# IMU.net
KiCad netlist of a schematic drawn in EAGLE
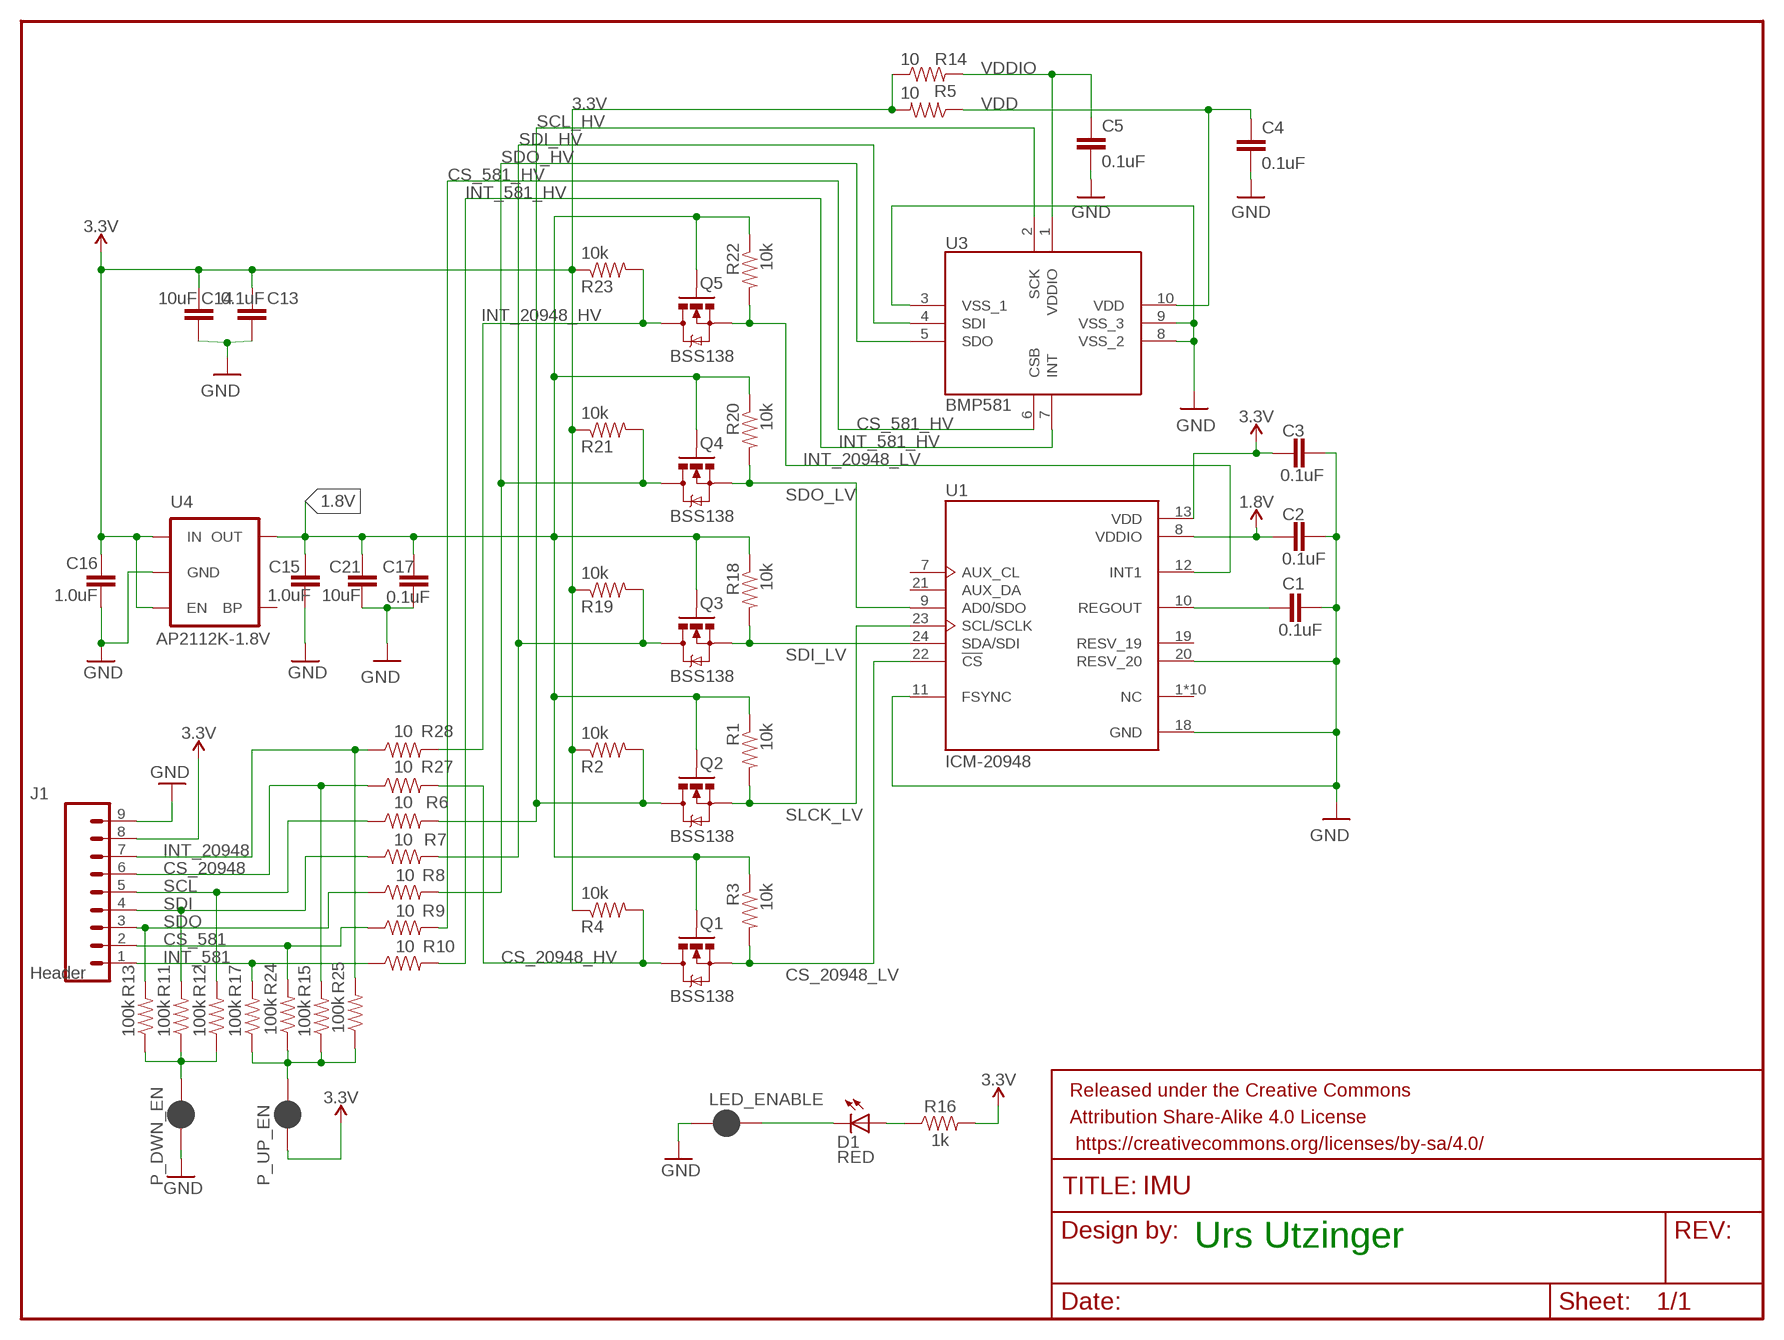
[diagram p0: schematic, sheet 1]

(export (version "E")
  (design (tool "Eeschema 10.0.6"))
  (components
    (comp (ref "C1")
      (value "0.1uF")
      (footprint "eagle-import:0603")
      (libsource (lib "eagle-import") (part "0.1UF-0603-25V-(+80/-20%)"))
    )
    (comp (ref "C2")
      (value "0.1uF")
      (footprint "eagle-import:0603")
      (libsource (lib "eagle-import") (part "0.1UF-0603-25V-(+80/-20%)"))
    )
    (comp (ref "C3")
      (value "0.1uF")
      (footprint "eagle-import:0603")
      (libsource (lib "eagle-import") (part "0.1UF-0603-25V-(+80/-20%)"))
    )
    (comp (ref "C4")
      (value "0.1uF")
      (footprint "eagle-import:0603")
      (libsource (lib "eagle-import") (part "0.1UF-0603-25V-(+80/-20%)"))
    )
    (comp (ref "C5")
      (value "0.1uF")
      (footprint "eagle-import:0603")
      (libsource (lib "eagle-import") (part "0.1UF-0603-25V-(+80/-20%)"))
    )
    (comp (ref "C13")
      (value "0.1uF")
      (footprint "eagle-import:0603")
      (libsource (lib "eagle-import") (part "0.1UF-0603-25V-(+80/-20%)"))
    )
    (comp (ref "C14")
      (value "10uF")
      (footprint "eagle-import:0603@1")
      (libsource (lib "eagle-import") (part "10UF-0603-6.3V-20%"))
    )
    (comp (ref "C15")
      (value "1.0uF")
      (footprint "eagle-import:0603")
      (libsource (lib "eagle-import") (part "1.0UF-0603-16V-10%"))
    )
    (comp (ref "C16")
      (value "1.0uF")
      (footprint "eagle-import:0603")
      (libsource (lib "eagle-import") (part "1.0UF-0603-16V-10%"))
    )
    (comp (ref "C17")
      (value "0.1uF")
      (footprint "eagle-import:0603")
      (libsource (lib "eagle-import") (part "0.1UF-0603-25V-(+80/-20%)"))
    )
    (comp (ref "C21")
      (value "10uF")
      (footprint "eagle-import:0603@1")
      (libsource (lib "eagle-import") (part "10UF-0603-6.3V-20%"))
    )
    (comp (ref "D1")
      (value "RED")
      (footprint "eagle-import:LED-0603")
      (libsource (lib "eagle-import") (part "LED-RED0603"))
    )
    (comp (ref "FRAME1")
      (value "FRAME-LETTERNO_PACKAGE")
      (footprint "eagle-import:DUMMY")
      (fields (field (name "DESIGNER") "Nobody"))
      (libsource (lib "eagle-import") (part "FRAME-LETTERNO_PACKAGE"))
    )
    (comp (ref "J1")
      (value "Header")
      (footprint "eagle-import:1X09")
      (libsource (lib "eagle-import") (part "CONN_09"))
    )
    (comp (ref "LED_ENABLE")
      (value "LED ENABLE")
      (footprint "eagle-import:SMT-JUMPER_2_NC_PASTE_SILK")
      (libsource (lib "eagle-import") (part "JUMPER-SMT_2_NC_PASTE_SILK"))
    )
    (comp (ref "P_DWN_EN")
      (value "JUMPER-SMT_2_NC_PASTE_SILK")
      (footprint "eagle-import:SMT-JUMPER_2_NC_PASTE_SILK")
      (libsource (lib "eagle-import") (part "JUMPER-SMT_2_NC_PASTE_SILK"))
    )
    (comp (ref "P_UP_EN")
      (value "JUMPER-SMT_2_NC_PASTE_SILK")
      (footprint "eagle-import:SMT-JUMPER_2_NC_PASTE_SILK")
      (libsource (lib "eagle-import") (part "JUMPER-SMT_2_NC_PASTE_SILK"))
    )
    (comp (ref "Q1")
      (value "BSS138")
      (footprint "eagle-import:SPARKFUN_SOT23-3")
      (libsource (lib "eagle-import") (part "SPARKFUN_MOSFET-NCHANNELSMD"))
    )
    (comp (ref "Q2")
      (value "BSS138")
      (footprint "eagle-import:SPARKFUN_SOT23-3")
      (libsource (lib "eagle-import") (part "SPARKFUN_MOSFET-NCHANNELSMD"))
    )
    (comp (ref "Q3")
      (value "BSS138")
      (footprint "eagle-import:SPARKFUN_SOT23-3")
      (libsource (lib "eagle-import") (part "SPARKFUN_MOSFET-NCHANNELSMD"))
    )
    (comp (ref "Q4")
      (value "BSS138")
      (footprint "eagle-import:SPARKFUN_SOT23-3")
      (libsource (lib "eagle-import") (part "SPARKFUN_MOSFET-NCHANNELSMD"))
    )
    (comp (ref "Q5")
      (value "BSS138")
      (footprint "eagle-import:SPARKFUN_SOT23-3")
      (libsource (lib "eagle-import") (part "SPARKFUN_MOSFET-NCHANNELSMD"))
    )
    (comp (ref "R1")
      (value "10k")
      (footprint "eagle-import:0603")
      (libsource (lib "eagle-import") (part "10KOHM-0603-1/10W-1%"))
    )
    (comp (ref "R2")
      (value "10k")
      (footprint "eagle-import:0603")
      (libsource (lib "eagle-import") (part "10KOHM-0603-1/10W-1%"))
    )
    (comp (ref "R3")
      (value "10k")
      (footprint "eagle-import:0603")
      (libsource (lib "eagle-import") (part "10KOHM-0603-1/10W-1%"))
    )
    (comp (ref "R4")
      (value "10k")
      (footprint "eagle-import:0603")
      (libsource (lib "eagle-import") (part "10KOHM-0603-1/10W-1%"))
    )
    (comp (ref "R5")
      (value "10")
      (footprint "eagle-import:0603")
      (libsource (lib "eagle-import") (part "10OHM-0603-1/10W-5%"))
    )
    (comp (ref "R6")
      (value "10")
      (footprint "eagle-import:0603")
      (libsource (lib "eagle-import") (part "10OHM-0603-1/10W-1%"))
    )
    (comp (ref "R7")
      (value "10")
      (footprint "eagle-import:0603")
      (libsource (lib "eagle-import") (part "10OHM-0603-1/10W-1%"))
    )
    (comp (ref "R8")
      (value "10")
      (footprint "eagle-import:0603")
      (libsource (lib "eagle-import") (part "10OHM-0603-1/10W-1%"))
    )
    (comp (ref "R9")
      (value "10")
      (footprint "eagle-import:0603")
      (libsource (lib "eagle-import") (part "10OHM-0603-1/10W-1%"))
    )
    (comp (ref "R10")
      (value "10")
      (footprint "eagle-import:0603")
      (libsource (lib "eagle-import") (part "10OHM-0603-1/10W-1%"))
    )
    (comp (ref "R11")
      (value "100k")
      (footprint "eagle-import:0603")
      (libsource (lib "eagle-import") (part "100KOHM-0603-1/10W-1%"))
    )
    (comp (ref "R12")
      (value "100k")
      (footprint "eagle-import:0603")
      (libsource (lib "eagle-import") (part "100KOHM-0603-1/10W-1%"))
    )
    (comp (ref "R13")
      (value "100k")
      (footprint "eagle-import:0603")
      (libsource (lib "eagle-import") (part "100KOHM-0603-1/10W-1%"))
    )
    (comp (ref "R14")
      (value "10")
      (footprint "eagle-import:0603")
      (libsource (lib "eagle-import") (part "10OHM-0603-1/10W-5%"))
    )
    (comp (ref "R15")
      (value "100k")
      (footprint "eagle-import:0603")
      (libsource (lib "eagle-import") (part "100KOHM-0603-1/10W-1%"))
    )
    (comp (ref "R16")
      (value "1k")
      (footprint "eagle-import:0603")
      (libsource (lib "eagle-import") (part "1KOHM-0603-1/10W-1%"))
    )
    (comp (ref "R17")
      (value "100k")
      (footprint "eagle-import:0603")
      (libsource (lib "eagle-import") (part "100KOHM-0603-1/10W-1%"))
    )
    (comp (ref "R18")
      (value "10k")
      (footprint "eagle-import:0603")
      (libsource (lib "eagle-import") (part "10KOHM-0603-1/10W-1%"))
    )
    (comp (ref "R19")
      (value "10k")
      (footprint "eagle-import:0603")
      (libsource (lib "eagle-import") (part "10KOHM-0603-1/10W-1%"))
    )
    (comp (ref "R20")
      (value "10k")
      (footprint "eagle-import:0603")
      (libsource (lib "eagle-import") (part "10KOHM-0603-1/10W-1%"))
    )
    (comp (ref "R21")
      (value "10k")
      (footprint "eagle-import:0603")
      (libsource (lib "eagle-import") (part "10KOHM-0603-1/10W-1%"))
    )
    (comp (ref "R22")
      (value "10k")
      (footprint "eagle-import:0603")
      (libsource (lib "eagle-import") (part "10KOHM-0603-1/10W-1%"))
    )
    (comp (ref "R23")
      (value "10k")
      (footprint "eagle-import:0603")
      (libsource (lib "eagle-import") (part "10KOHM-0603-1/10W-1%"))
    )
    (comp (ref "R24")
      (value "100k")
      (footprint "eagle-import:0603")
      (libsource (lib "eagle-import") (part "100KOHM-0603-1/10W-1%"))
    )
    (comp (ref "R25")
      (value "100k")
      (footprint "eagle-import:0603")
      (libsource (lib "eagle-import") (part "100KOHM-0603-1/10W-1%"))
    )
    (comp (ref "R27")
      (value "10")
      (footprint "eagle-import:0603")
      (libsource (lib "eagle-import") (part "10OHM-0603-1/10W-1%"))
    )
    (comp (ref "R28")
      (value "10")
      (footprint "eagle-import:0603")
      (libsource (lib "eagle-import") (part "10OHM-0603-1/10W-1%"))
    )
    (comp (ref "U1")
      (value "ICM-20948")
      (footprint "eagle-import:QFN40P300X300X105-24N")
      (fields (field (name "MANUFACTURER") "TDK InvenSense"))
      (libsource (lib "eagle-import") (part "ICM-20948"))
    )
    (comp (ref "U3")
      (value "BMP581")
      (footprint "eagle-import:BMP581")
      (fields (field (name "MOUSER_PART_NUMBER") "262-BMP581"))
      (libsource (lib "eagle-import") (part "BMP581"))
    )
    (comp (ref "U4")
      (value "AP2112K-1.8V")
      (footprint "eagle-import:SOT23-5")
      (libsource (lib "eagle-import") (part "V_REG_LDOSMD"))
    )
  )
  (nets
    (net (code "1") (name "/CS_581") (class "Default")
      (node (ref "J1") (pin "2") (pinfunction "2_2") (pintype "passive"))
      (node (ref "R24") (pin "2") (pinfunction "2_2") (pintype "passive"))
      (node (ref "R9") (pin "1") (pinfunction "1_1") (pintype "passive"))
    )
    (net (code "2") (name "/CS_581_HV") (class "Default")
      (node (ref "R9") (pin "2") (pinfunction "2_2") (pintype "passive"))
      (node (ref "U3") (pin "6") (pinfunction "CSB_6") (pintype "bidirectional"))
    )
    (net (code "3") (name "/CS_20948") (class "Default")
      (node (ref "J1") (pin "6") (pinfunction "6_6") (pintype "passive"))
      (node (ref "R15") (pin "2") (pinfunction "2_2") (pintype "passive"))
      (node (ref "R27") (pin "1") (pinfunction "1_1") (pintype "passive"))
    )
    (net (code "4") (name "/CS_20948_HV") (class "Default")
      (node (ref "Q1") (pin "3") (pinfunction "D_3") (pintype "passive"))
      (node (ref "R27") (pin "2") (pinfunction "2_2") (pintype "passive"))
      (node (ref "R4") (pin "2") (pinfunction "2_2") (pintype "passive"))
    )
    (net (code "5") (name "/CS_20948_LV") (class "Default")
      (node (ref "Q1") (pin "2") (pinfunction "S_2") (pintype "passive"))
      (node (ref "R3") (pin "2") (pinfunction "2_2") (pintype "passive"))
      (node (ref "U1") (pin "22") (pinfunction "~{CS}_22") (pintype "input"))
    )
    (net (code "6") (name "/INT_581") (class "Default")
      (node (ref "J1") (pin "1") (pinfunction "1_1") (pintype "passive"))
      (node (ref "R10") (pin "1") (pinfunction "1_1") (pintype "passive"))
      (node (ref "R17") (pin "2") (pinfunction "2_2") (pintype "passive"))
    )
    (net (code "7") (name "/INT_581_HV") (class "Default")
      (node (ref "R10") (pin "2") (pinfunction "2_2") (pintype "passive"))
      (node (ref "U3") (pin "7") (pinfunction "INT_7") (pintype "bidirectional"))
    )
    (net (code "8") (name "/INT_20948") (class "Default")
      (node (ref "J1") (pin "7") (pinfunction "7_7") (pintype "passive"))
      (node (ref "R25") (pin "2") (pinfunction "2_2") (pintype "passive"))
      (node (ref "R28") (pin "1") (pinfunction "1_1") (pintype "passive"))
    )
    (net (code "9") (name "/INT_20948_HV") (class "Default")
      (node (ref "Q5") (pin "3") (pinfunction "D_3") (pintype "passive"))
      (node (ref "R23") (pin "2") (pinfunction "2_2") (pintype "passive"))
      (node (ref "R28") (pin "2") (pinfunction "2_2") (pintype "passive"))
    )
    (net (code "10") (name "/INT_20948_LV") (class "Default")
      (node (ref "Q5") (pin "2") (pinfunction "S_2") (pintype "passive"))
      (node (ref "R22") (pin "2") (pinfunction "2_2") (pintype "passive"))
      (node (ref "U1") (pin "12") (pinfunction "INT1_12") (pintype "output"))
    )
    (net (code "11") (name "/SCL") (class "Default")
      (node (ref "J1") (pin "5") (pinfunction "5_5") (pintype "passive"))
      (node (ref "R12") (pin "2") (pinfunction "2_2") (pintype "passive"))
      (node (ref "R6") (pin "1") (pinfunction "1_1") (pintype "passive"))
    )
    (net (code "12") (name "/SCL_HV") (class "Default")
      (node (ref "Q2") (pin "3") (pinfunction "D_3") (pintype "passive"))
      (node (ref "R2") (pin "2") (pinfunction "2_2") (pintype "passive"))
      (node (ref "R6") (pin "2") (pinfunction "2_2") (pintype "passive"))
      (node (ref "U3") (pin "2") (pinfunction "SCK_2") (pintype "bidirectional"))
    )
    (net (code "13") (name "/SDI") (class "Default")
      (node (ref "J1") (pin "4") (pinfunction "4_4") (pintype "passive"))
      (node (ref "R11") (pin "2") (pinfunction "2_2") (pintype "passive"))
      (node (ref "R7") (pin "1") (pinfunction "1_1") (pintype "passive"))
    )
    (net (code "14") (name "/SDI_HV") (class "Default")
      (node (ref "Q3") (pin "3") (pinfunction "D_3") (pintype "passive"))
      (node (ref "R19") (pin "2") (pinfunction "2_2") (pintype "passive"))
      (node (ref "R7") (pin "2") (pinfunction "2_2") (pintype "passive"))
      (node (ref "U3") (pin "4") (pinfunction "SDI_4") (pintype "bidirectional"))
    )
    (net (code "15") (name "/SDI_LV") (class "Default")
      (node (ref "Q3") (pin "2") (pinfunction "S_2") (pintype "passive"))
      (node (ref "R18") (pin "2") (pinfunction "2_2") (pintype "passive"))
      (node (ref "U1") (pin "24") (pinfunction "SDA/SDI_24") (pintype "bidirectional"))
    )
    (net (code "16") (name "/SDO") (class "Default")
      (node (ref "J1") (pin "3") (pinfunction "3_3") (pintype "passive"))
      (node (ref "R13") (pin "2") (pinfunction "2_2") (pintype "passive"))
      (node (ref "R8") (pin "1") (pinfunction "1_1") (pintype "passive"))
    )
    (net (code "17") (name "/SDO_HV") (class "Default")
      (node (ref "Q4") (pin "3") (pinfunction "D_3") (pintype "passive"))
      (node (ref "R21") (pin "2") (pinfunction "2_2") (pintype "passive"))
      (node (ref "R8") (pin "2") (pinfunction "2_2") (pintype "passive"))
      (node (ref "U3") (pin "5") (pinfunction "SDO_5") (pintype "bidirectional"))
    )
    (net (code "18") (name "/SDO_LV") (class "Default")
      (node (ref "Q4") (pin "2") (pinfunction "S_2") (pintype "passive"))
      (node (ref "R20") (pin "2") (pinfunction "2_2") (pintype "passive"))
      (node (ref "U1") (pin "9") (pinfunction "AD0/SDO_9") (pintype "bidirectional"))
    )
    (net (code "19") (name "/SLCK_LV") (class "Default")
      (node (ref "Q2") (pin "2") (pinfunction "S_2") (pintype "passive"))
      (node (ref "R1") (pin "2") (pinfunction "2_2") (pintype "passive"))
      (node (ref "U1") (pin "23") (pinfunction "SCL/SCLK_23") (pintype "input"))
    )
    (net (code "20") (name "/VDD") (class "Default")
      (node (ref "C4") (pin "1") (pinfunction "1_1") (pintype "passive"))
      (node (ref "R5") (pin "1") (pinfunction "1_1") (pintype "passive"))
      (node (ref "U3") (pin "10") (pinfunction "VDD_10") (pintype "bidirectional"))
    )
    (net (code "21") (name "/VDDIO") (class "Default")
      (node (ref "C5") (pin "1") (pinfunction "1_1") (pintype "passive"))
      (node (ref "R14") (pin "2") (pinfunction "2_2") (pintype "passive"))
      (node (ref "U3") (pin "1") (pinfunction "VDDIO_1") (pintype "bidirectional"))
    )
    (net (code "22") (name "1.8V") (class "Default")
      (node (ref "C15") (pin "2") (pinfunction "2_2") (pintype "passive"))
      (node (ref "C17") (pin "1") (pinfunction "1_1") (pintype "passive"))
      (node (ref "C2") (pin "1") (pinfunction "1_1") (pintype "passive"))
      (node (ref "C21") (pin "1") (pinfunction "1_1") (pintype "passive"))
      (node (ref "Q1") (pin "1") (pinfunction "G_1") (pintype "passive"))
      (node (ref "Q2") (pin "1") (pinfunction "G_1") (pintype "passive"))
      (node (ref "Q3") (pin "1") (pinfunction "G_1") (pintype "passive"))
      (node (ref "Q4") (pin "1") (pinfunction "G_1") (pintype "passive"))
      (node (ref "Q5") (pin "1") (pinfunction "G_1") (pintype "passive"))
      (node (ref "R1") (pin "1") (pinfunction "1_1") (pintype "passive"))
      (node (ref "R18") (pin "1") (pinfunction "1_1") (pintype "passive"))
      (node (ref "R20") (pin "1") (pinfunction "1_1") (pintype "passive"))
      (node (ref "R22") (pin "1") (pinfunction "1_1") (pintype "passive"))
      (node (ref "R3") (pin "1") (pinfunction "1_1") (pintype "passive"))
      (node (ref "U1") (pin "8") (pinfunction "VDDIO_8") (pintype "power_in"))
      (node (ref "U4") (pin "5") (pinfunction "OUT_5") (pintype "passive"))
    )
    (net (code "23") (name "3.3V") (class "Default")
      (node (ref "C13") (pin "1") (pinfunction "1_1") (pintype "passive"))
      (node (ref "C14") (pin "1") (pinfunction "1_1") (pintype "passive"))
      (node (ref "C16") (pin "2") (pinfunction "2_2") (pintype "passive"))
      (node (ref "C3") (pin "1") (pinfunction "1_1") (pintype "passive"))
      (node (ref "J1") (pin "8") (pinfunction "8_8") (pintype "passive"))
      (node (ref "P_UP_EN") (pin "1") (pinfunction "1_1") (pintype "passive"))
      (node (ref "R14") (pin "1") (pinfunction "1_1") (pintype "passive"))
      (node (ref "R16") (pin "2") (pinfunction "2_2") (pintype "passive"))
      (node (ref "R19") (pin "1") (pinfunction "1_1") (pintype "passive"))
      (node (ref "R2") (pin "1") (pinfunction "1_1") (pintype "passive"))
      (node (ref "R21") (pin "1") (pinfunction "1_1") (pintype "passive"))
      (node (ref "R23") (pin "1") (pinfunction "1_1") (pintype "passive"))
      (node (ref "R4") (pin "1") (pinfunction "1_1") (pintype "passive"))
      (node (ref "R5") (pin "2") (pinfunction "2_2") (pintype "passive"))
      (node (ref "U1") (pin "13") (pinfunction "VDD_13") (pintype "power_in"))
      (node (ref "U4") (pin "1") (pinfunction "IN_1") (pintype "input"))
      (node (ref "U4") (pin "3") (pinfunction "EN_3") (pintype "input"))
    )
    (net (code "24") (name "GND") (class "Default")
      (node (ref "C1") (pin "2") (pinfunction "2_2") (pintype "passive"))
      (node (ref "C13") (pin "2") (pinfunction "2_2") (pintype "passive"))
      (node (ref "C14") (pin "2") (pinfunction "2_2") (pintype "passive"))
      (node (ref "C15") (pin "1") (pinfunction "1_1") (pintype "passive"))
      (node (ref "C16") (pin "1") (pinfunction "1_1") (pintype "passive"))
      (node (ref "C17") (pin "2") (pinfunction "2_2") (pintype "passive"))
      (node (ref "C2") (pin "2") (pinfunction "2_2") (pintype "passive"))
      (node (ref "C21") (pin "2") (pinfunction "2_2") (pintype "passive"))
      (node (ref "C3") (pin "2") (pinfunction "2_2") (pintype "passive"))
      (node (ref "C4") (pin "2") (pinfunction "2_2") (pintype "passive"))
      (node (ref "C5") (pin "2") (pinfunction "2_2") (pintype "passive"))
      (node (ref "J1") (pin "9") (pinfunction "9_9") (pintype "passive"))
      (node (ref "LED_ENABLE") (pin "1") (pinfunction "1_1") (pintype "passive"))
      (node (ref "P_DWN_EN") (pin "1") (pinfunction "1_1") (pintype "passive"))
      (node (ref "U1") (pin "11") (pinfunction "FSYNC_11") (pintype "input"))
      (node (ref "U1") (pin "18") (pinfunction "GND_18") (pintype "power_in"))
      (node (ref "U1") (pin "20") (pinfunction "RESV_20_20") (pintype "passive"))
      (node (ref "U3") (pin "3") (pinfunction "VSS_1_3") (pintype "bidirectional"))
      (node (ref "U3") (pin "8") (pinfunction "VSS_2_8") (pintype "bidirectional"))
      (node (ref "U3") (pin "9") (pinfunction "VSS_3_9") (pintype "bidirectional"))
      (node (ref "U4") (pin "2") (pinfunction "GND_2") (pintype "input"))
    )
    (net (code "25") (name "Net-(D1-PadA)") (class "Default")
      (node (ref "D1") (pin "A") (pinfunction "A_A") (pintype "passive"))
      (node (ref "R16") (pin "1") (pinfunction "1_1") (pintype "passive"))
    )
    (net (code "26") (name "Net-(D1-PadC)") (class "Default")
      (node (ref "D1") (pin "C") (pinfunction "C_C") (pintype "passive"))
      (node (ref "LED_ENABLE") (pin "2") (pinfunction "2_2") (pintype "passive"))
    )
    (net (code "27") (name "Net-(P_DWN_EN-Pad2)") (class "Default")
      (node (ref "P_DWN_EN") (pin "2") (pinfunction "2_2") (pintype "passive"))
      (node (ref "R11") (pin "1") (pinfunction "1_1") (pintype "passive"))
      (node (ref "R12") (pin "1") (pinfunction "1_1") (pintype "passive"))
      (node (ref "R13") (pin "1") (pinfunction "1_1") (pintype "passive"))
    )
    (net (code "28") (name "Net-(P_UP_EN-Pad2)") (class "Default")
      (node (ref "P_UP_EN") (pin "2") (pinfunction "2_2") (pintype "passive"))
      (node (ref "R15") (pin "1") (pinfunction "1_1") (pintype "passive"))
      (node (ref "R17") (pin "1") (pinfunction "1_1") (pintype "passive"))
      (node (ref "R24") (pin "1") (pinfunction "1_1") (pintype "passive"))
      (node (ref "R25") (pin "1") (pinfunction "1_1") (pintype "passive"))
    )
    (net (code "29") (name "Net-(U1-REGOUT)") (class "Default")
      (node (ref "C1") (pin "1") (pinfunction "1_1") (pintype "passive"))
      (node (ref "U1") (pin "10") (pinfunction "REGOUT_10") (pintype "output"))
    )
    (net (code "30") (name "unconnected-(U1-AUX_CL-Pad7)") (class "Default")
      (node (ref "U1") (pin "7") (pinfunction "AUX_CL_7") (pintype "input"))
    )
    (net (code "31") (name "unconnected-(U1-AUX_DA-Pad21)") (class "Default")
      (node (ref "U1") (pin "21") (pinfunction "AUX_DA_21") (pintype "bidirectional"))
    )
    (net (code "32") (name "unconnected-(U1-NC-Pad1)") (class "Default")
      (node (ref "U1") (pin "1") (pinfunction "NC_1") (pintype "no_connect"))
    )
    (net (code "33") (name "unconnected-(U1-NC-Pad2)") (class "Default")
      (node (ref "U1") (pin "2") (pinfunction "NC_2") (pintype "no_connect"))
    )
    (net (code "34") (name "unconnected-(U1-NC-Pad3)") (class "Default")
      (node (ref "U1") (pin "3") (pinfunction "NC_3") (pintype "no_connect"))
    )
    (net (code "35") (name "unconnected-(U1-NC-Pad4)") (class "Default")
      (node (ref "U1") (pin "4") (pinfunction "NC_4") (pintype "no_connect"))
    )
    (net (code "36") (name "unconnected-(U1-NC-Pad5)") (class "Default")
      (node (ref "U1") (pin "5") (pinfunction "NC_5") (pintype "no_connect"))
    )
    (net (code "37") (name "unconnected-(U1-NC-Pad6)") (class "Default")
      (node (ref "U1") (pin "6") (pinfunction "NC_6") (pintype "no_connect"))
    )
    (net (code "38") (name "unconnected-(U1-NC-Pad14)") (class "Default")
      (node (ref "U1") (pin "14") (pinfunction "NC_14") (pintype "no_connect"))
    )
    (net (code "39") (name "unconnected-(U1-NC-Pad15)") (class "Default")
      (node (ref "U1") (pin "15") (pinfunction "NC_15") (pintype "no_connect"))
    )
    (net (code "40") (name "unconnected-(U1-NC-Pad16)") (class "Default")
      (node (ref "U1") (pin "16") (pinfunction "NC_16") (pintype "no_connect"))
    )
    (net (code "41") (name "unconnected-(U1-NC-Pad17)") (class "Default")
      (node (ref "U1") (pin "17") (pinfunction "NC_17") (pintype "no_connect"))
    )
    (net (code "42") (name "unconnected-(U1-RESV_19-Pad19)") (class "Default")
      (node (ref "U1") (pin "19") (pinfunction "RESV_19_19") (pintype "passive"))
    )
    (net (code "43") (name "unconnected-(U4-BP-Pad4)") (class "Default")
      (node (ref "U4") (pin "4") (pinfunction "BP_4") (pintype "input"))
    )
  )
)
